# design.net
KiCad netlist of a schematic drawn in Altium Designer
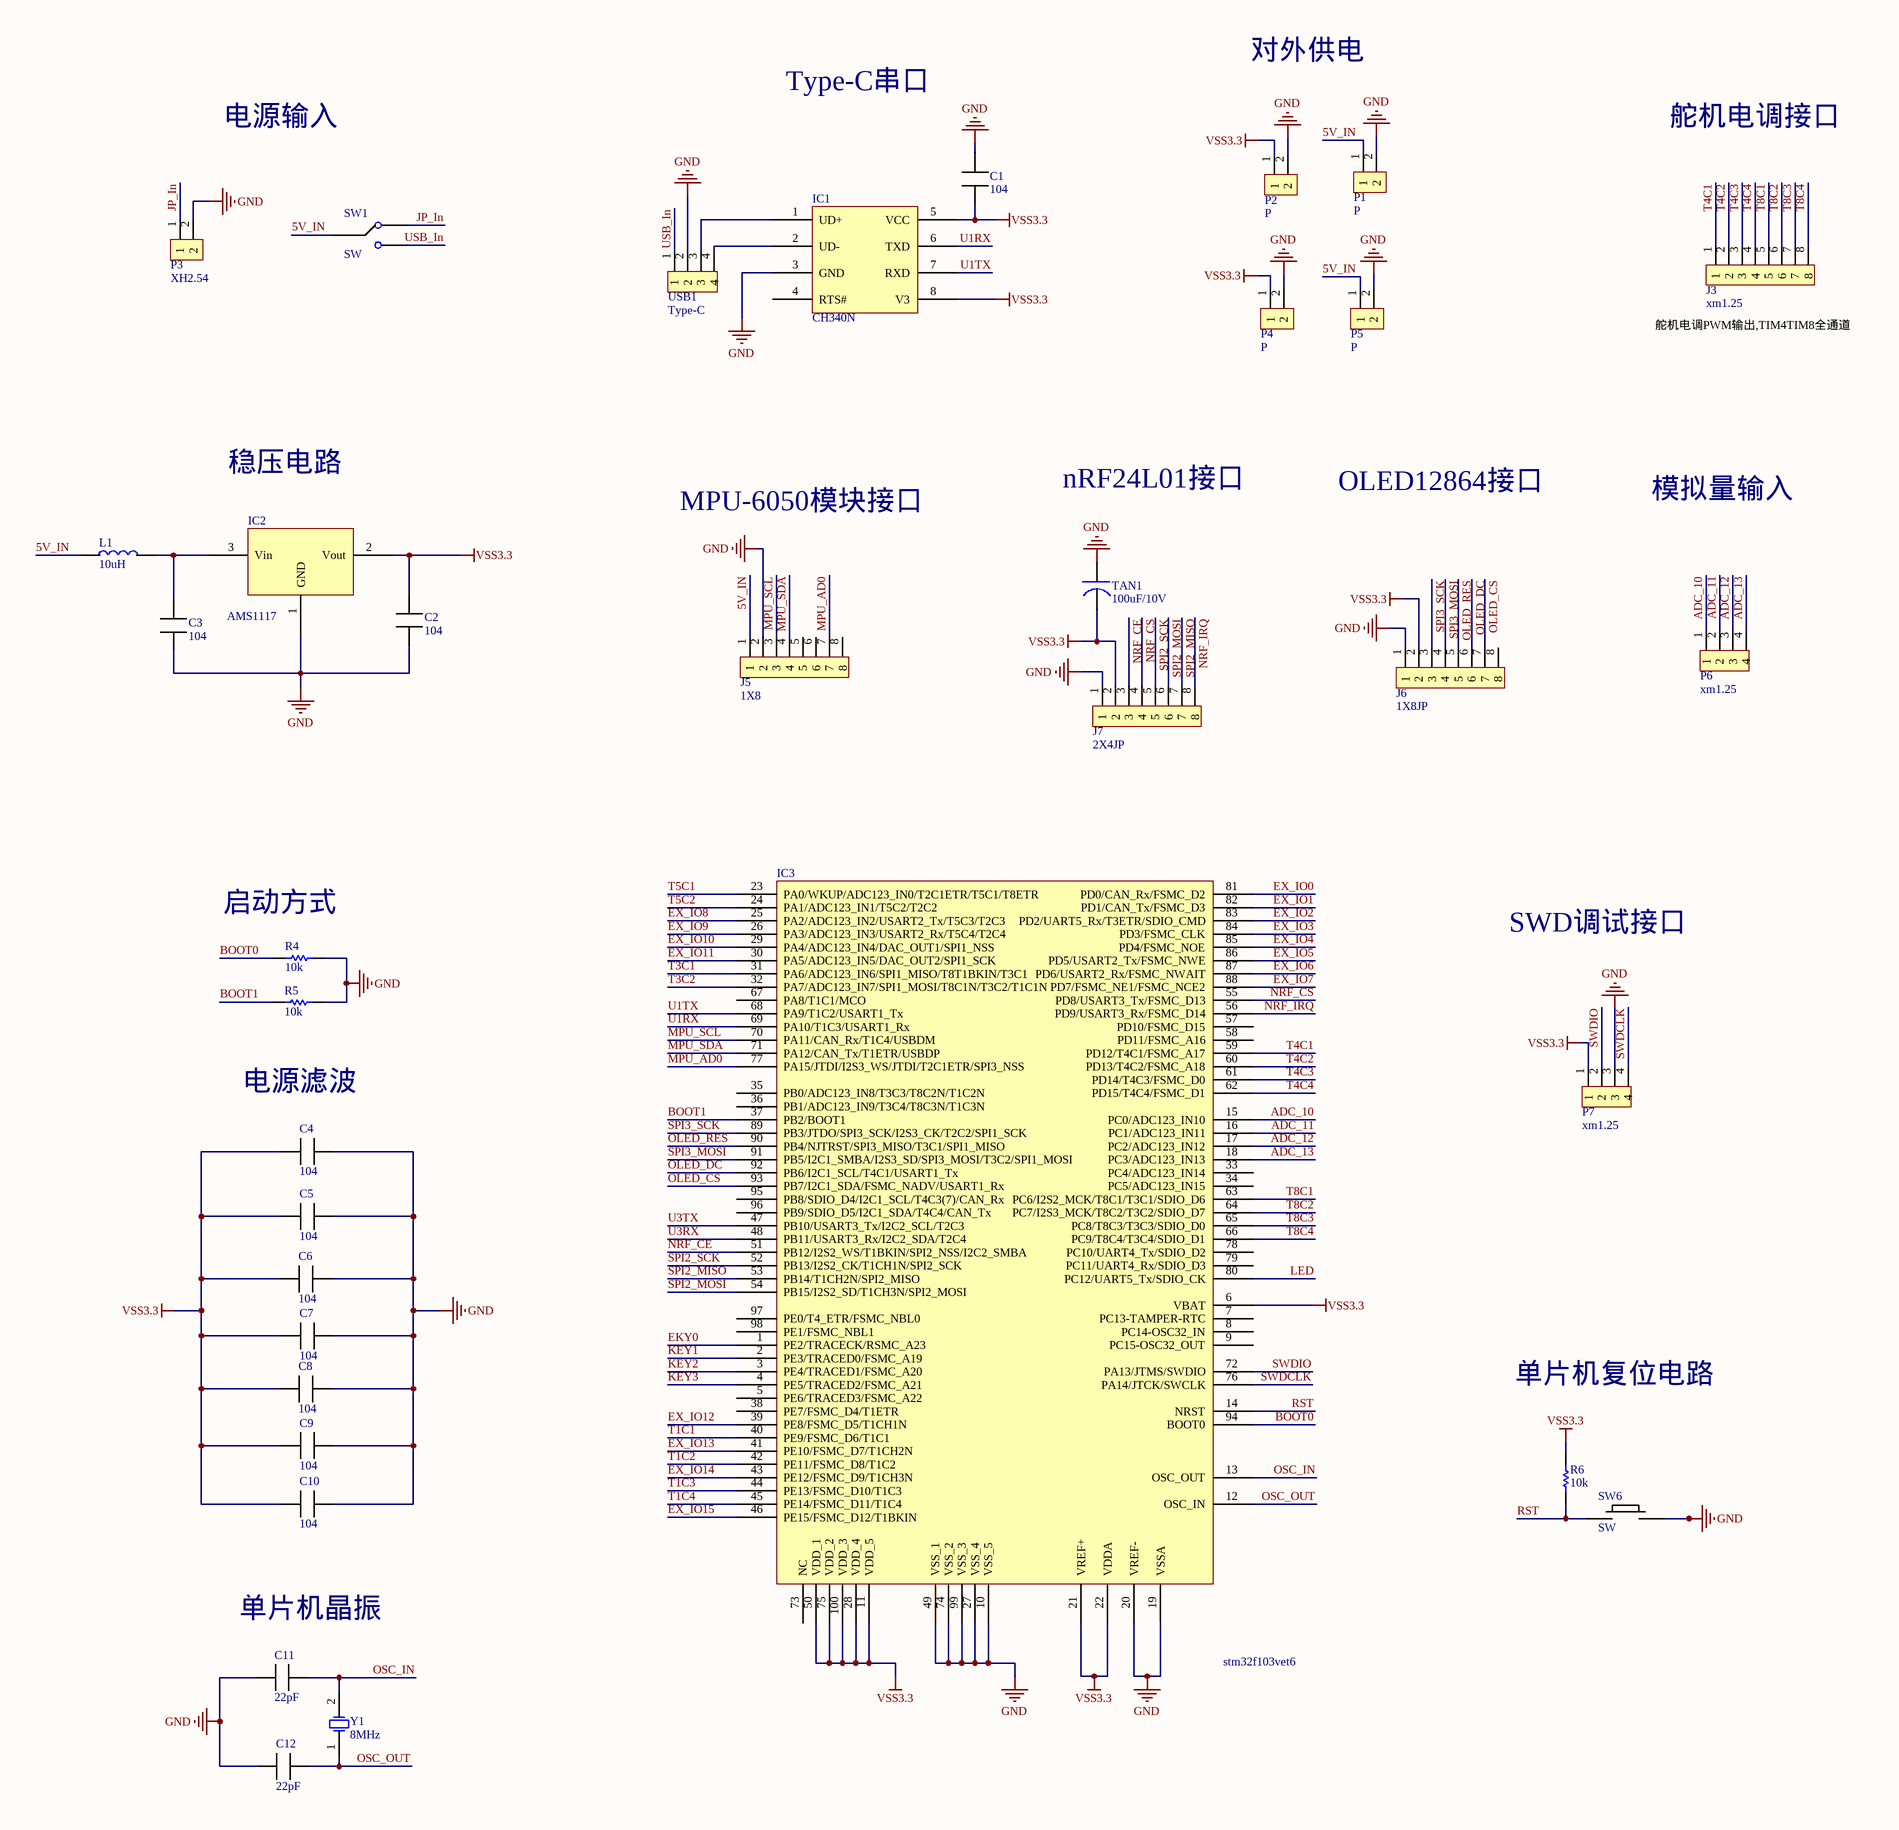
[diagram p0: 船核心板.SchDoc, left]
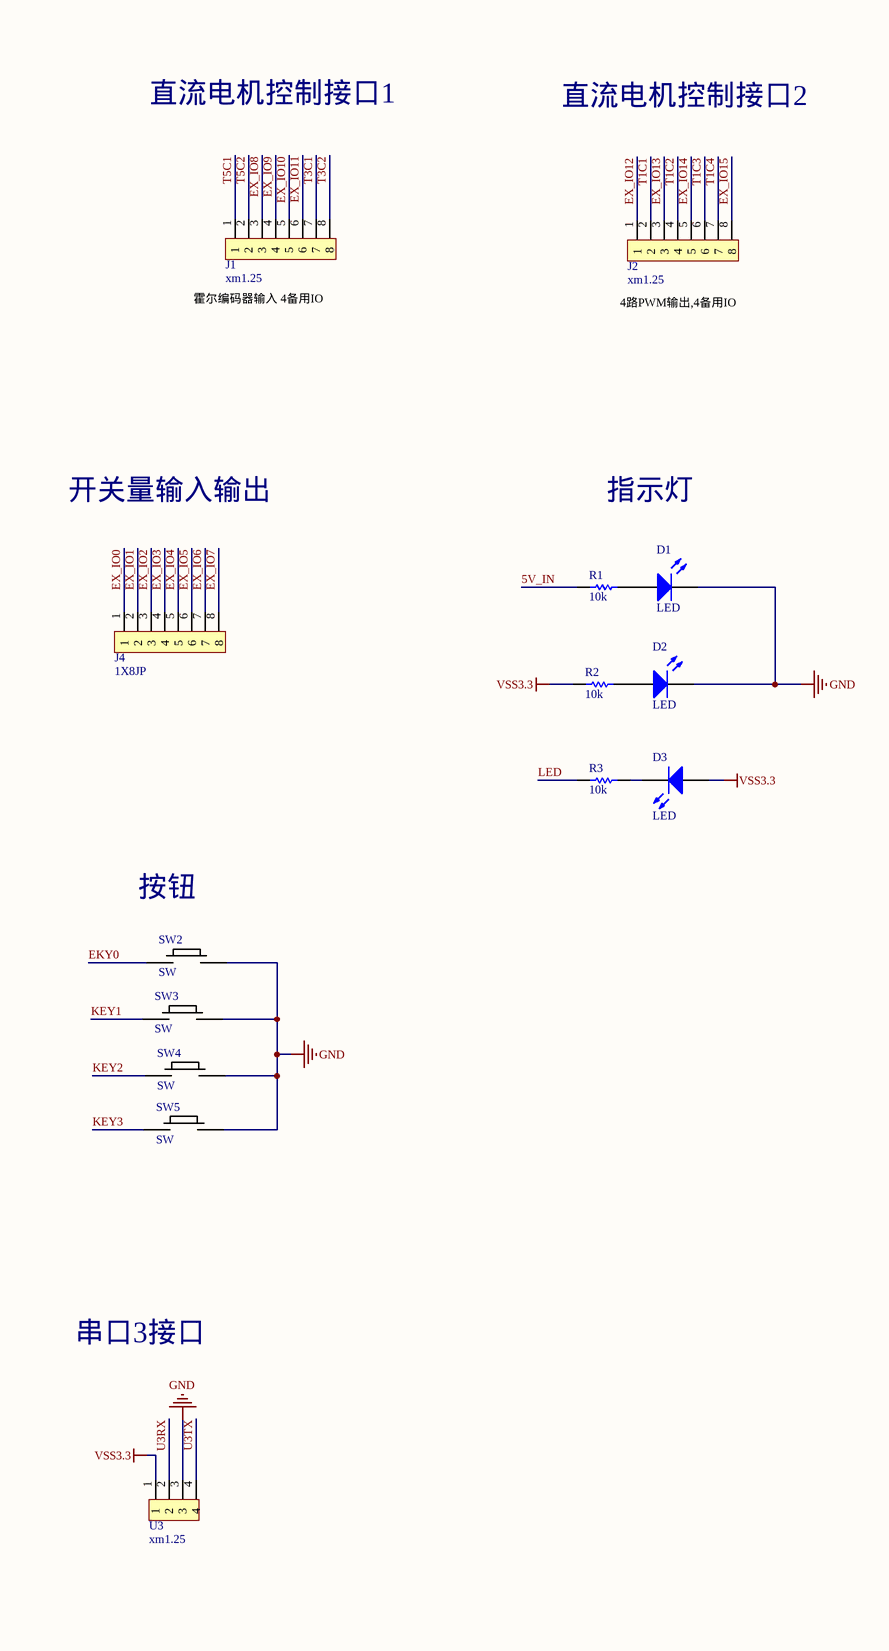
[diagram p1: 船核心板.SchDoc, right]

(export (version "E")
  (design (tool "Eeschema 10.0.6"))
  (components
    (comp (ref "C1") (value "104") (footprint "C 0603") (libsource (lib "船核心板") (part "电容")))
    (comp (ref "C2") (value "104") (footprint "C 0603") (libsource (lib "船核心板") (part "电容")))
    (comp (ref "C3") (value "104") (footprint "C 0603") (libsource (lib "船核心板") (part "电容")))
    (comp (ref "C4") (value "104") (footprint "C 0603") (libsource (lib "船核心板") (part "电容")))
    (comp (ref "C5") (value "104") (footprint "C 0603") (libsource (lib "船核心板") (part "电容")))
    (comp (ref "C6") (value "104") (footprint "C 0603") (libsource (lib "船核心板") (part "电容")))
    (comp (ref "C7") (value "104") (footprint "C 0603") (libsource (lib "船核心板") (part "电容")))
    (comp (ref "C8") (value "104") (footprint "C 0603") (libsource (lib "船核心板") (part "电容")))
    (comp (ref "C9") (value "104") (footprint "C 0603") (libsource (lib "船核心板") (part "电容")))
    (comp (ref "C10") (value "104") (footprint "C 0603") (libsource (lib "船核心板") (part "电容")))
    (comp (ref "C11") (value "22pF") (footprint "C 0603") (libsource (lib "船核心板") (part "电容")))
    (comp (ref "C12") (value "22pF") (footprint "C 0603") (libsource (lib "船核心板") (part "电容")))
    (comp (ref "D1")
      (value "LED")
      (footprint "LED 0603")
      (description "Typical INFRARED GaAs LED")
      (fields (field (name "PUBLISHER") "Altium Limited"))
      (libsource (lib "船核心板") (part "LED"))
    )
    (comp (ref "D2")
      (value "LED")
      (footprint "LED 0603")
      (description "Typical INFRARED GaAs LED")
      (fields (field (name "PUBLISHER") "Altium Limited"))
      (libsource (lib "船核心板") (part "LED"))
    )
    (comp (ref "D3")
      (value "LED")
      (footprint "LED 0603")
      (description "Typical INFRARED GaAs LED")
      (fields (field (name "PUBLISHER") "Altium Limited"))
      (libsource (lib "船核心板") (part "LED"))
    )
    (comp (ref "IC1") (value "CH340N") (footprint "SOP-8") (libsource (lib "船核心板") (part "CH340N")))
    (comp (ref "IC2") (value "AMS1117") (footprint "SOT-223") (libsource (lib "船核心板") (part "AMS1117-3.3")))
    (comp (ref "IC3")
      (value "stm32f103vet6")
      (footprint "LQPF100 12X12")
      (libsource (lib "altium-import") (part "root_0_stm32f103vet6_"))
    )
    (comp (ref "J1") (value "xm1.25") (footprint "MX1.25 8P") (libsource (lib "船核心板") (part "1X8排针")))
    (comp (ref "J2") (value "xm1.25") (footprint "MX1.25 8P") (libsource (lib "船核心板") (part "1X8排针")))
    (comp (ref "J3") (value "xm1.25") (footprint "MX1.25 8P") (libsource (lib "船核心板") (part "1X8排针")))
    (comp (ref "J4") (value "1X8JP") (footprint "HDR2.54-M-LI-8P") (libsource (lib "船核心板") (part "1X8排针")))
    (comp (ref "J5") (value "1X8") (footprint "HDR2.54-M-LI-8P") (libsource (lib "船核心板") (part "1X8排针")))
    (comp (ref "J6") (value "1X8JP") (footprint "HDR2.54-M-LI-8P") (libsource (lib "船核心板") (part "1X8排针")))
    (comp (ref "J7") (value "2X4JP") (footprint "HDR2.54-LI-2x4P") (libsource (lib "船核心板") (part "1X8排针")))
    (comp (ref "L1") (value "10uH") (footprint "L 0603") (libsource (lib "船核心板") (part "电感")))
    (comp (ref "P1") (value "P") (footprint "XH2.54 2P") (libsource (lib "船核心板") (part "1X2排针")))
    (comp (ref "P2") (value "P") (footprint "XH2.54 2P") (libsource (lib "船核心板") (part "1X2排针")))
    (comp (ref "P3") (value "XH2.54") (footprint "XH2.54 2P") (libsource (lib "船核心板") (part "1X2排针")))
    (comp (ref "P4") (value "P") (footprint "XH2.54 2P") (libsource (lib "船核心板") (part "1X2排针")))
    (comp (ref "P5") (value "P") (footprint "XH2.54 2P") (libsource (lib "船核心板") (part "1X2排针")))
    (comp (ref "P6") (value "xm1.25") (footprint "MX1.25") (libsource (lib "船核心板") (part "1X4排针")))
    (comp (ref "P7") (value "xm1.25") (footprint "MX1.25") (libsource (lib "船核心板") (part "1X4排针")))
    (comp (ref "R1")
      (value "10k")
      (footprint "R 0603")
      (description "Resistor")
      (fields (field (name "PUBLISHER") "Altium Limited"))
      (libsource (lib "船核心板") (part "Res"))
    )
    (comp (ref "R2")
      (value "10k")
      (footprint "R 0603")
      (description "Resistor")
      (fields (field (name "PUBLISHER") "Altium Limited"))
      (libsource (lib "船核心板") (part "Res"))
    )
    (comp (ref "R3")
      (value "10k")
      (footprint "R 0603")
      (description "Resistor")
      (fields (field (name "PUBLISHER") "Altium Limited"))
      (libsource (lib "船核心板") (part "Res"))
    )
    (comp (ref "R4")
      (value "10k")
      (footprint "R 0603")
      (description "Resistor")
      (fields (field (name "PUBLISHER") "Altium Limited"))
      (libsource (lib "船核心板") (part "Res"))
    )
    (comp (ref "R5")
      (value "10k")
      (footprint "R 0603")
      (description "Resistor")
      (fields (field (name "PUBLISHER") "Altium Limited"))
      (libsource (lib "船核心板") (part "Res"))
    )
    (comp (ref "R6")
      (value "10k")
      (footprint "R 0603")
      (description "Resistor")
      (fields (field (name "PUBLISHER") "Altium Limited"))
      (libsource (lib "船核心板") (part "Res"))
    )
    (comp (ref "SW1") (value "SW") (footprint "拨动开关 9X3.5X3.5 侧卧") (libsource (lib "船核心板") (part "单刀双置开关")))
    (comp (ref "SW2") (value "SW") (footprint "SW SMD 3x6x2.5") (libsource (lib "船核心板") (part "弹簧开关")))
    (comp (ref "SW3") (value "SW") (footprint "SW SMD 3x6x2.5") (libsource (lib "船核心板") (part "弹簧开关")))
    (comp (ref "SW4") (value "SW") (footprint "SW SMD 3x6x2.5") (libsource (lib "船核心板") (part "弹簧开关")))
    (comp (ref "SW5") (value "SW") (footprint "SW SMD 3x6x2.5") (libsource (lib "船核心板") (part "弹簧开关")))
    (comp (ref "SW6") (value "SW") (footprint "SW SMD 3x6x2.5") (libsource (lib "船核心板") (part "弹簧开关")))
    (comp (ref "TAN1")
      (value "100uF/10V")
      (footprint "6.3*5.4mm 电解电容")
      (libsource (lib "船核心板") (part "极性电容"))
    )
    (comp (ref "U3") (value "xm1.25") (footprint "2.54 _ 4Pin") (libsource (lib "船核心板") (part "1X4排针")))
    (comp (ref "USB1") (value "Type-C") (footprint "USB Type-C") (libsource (lib "船核心板") (part "1X4排针")))
    (comp (ref "Y1")
      (value "8MHz")
      (footprint "OSC SMD")
      (description "Crystal Oscillator")
      (fields (field (name "PUBLISHER") "Altium Limited"))
      (libsource (lib "船核心板") (part "晶振"))
    )
  )
  (nets
    (net (code "1") (name "/5V_IN") (class "Default")
      (node (ref "J5") (pin "1") (pinfunction "1_1") (pintype "passive"))
      (node (ref "L1") (pin "1") (pinfunction "1_1") (pintype "passive"))
      (node (ref "P1") (pin "1") (pinfunction "1_1") (pintype "passive"))
      (node (ref "P5") (pin "1") (pinfunction "1_1") (pintype "passive"))
      (node (ref "R1") (pin "1") (pinfunction "1_1") (pintype "passive"))
      (node (ref "SW1") (pin "1") (pinfunction "1_1") (pintype "passive"))
    )
    (net (code "2") (name "/ADC_10") (class "Default")
      (node (ref "IC3") (pin "15") (pinfunction "PC0/ADC123_IN10_15") (pintype "passive"))
      (node (ref "P6") (pin "1") (pinfunction "1_1") (pintype "passive"))
    )
    (net (code "3") (name "/ADC_11") (class "Default")
      (node (ref "IC3") (pin "16") (pinfunction "PC1/ADC123_IN11_16") (pintype "passive"))
      (node (ref "P6") (pin "2") (pinfunction "2_2") (pintype "passive"))
    )
    (net (code "4") (name "/ADC_12") (class "Default")
      (node (ref "IC3") (pin "17") (pinfunction "PC2/ADC123_IN12_17") (pintype "passive"))
      (node (ref "P6") (pin "3") (pinfunction "3_3") (pintype "passive"))
    )
    (net (code "5") (name "/ADC_13") (class "Default")
      (node (ref "IC3") (pin "18") (pinfunction "PC3/ADC123_IN13_18") (pintype "passive"))
      (node (ref "P6") (pin "4") (pinfunction "4_4") (pintype "passive"))
    )
    (net (code "6") (name "/BOOT0") (class "Default")
      (node (ref "IC3") (pin "94") (pinfunction "BOOT0_94") (pintype "passive"))
      (node (ref "R4") (pin "1") (pinfunction "1_1") (pintype "passive"))
    )
    (net (code "7") (name "/BOOT1") (class "Default")
      (node (ref "IC3") (pin "37") (pinfunction "PB2/BOOT1_37") (pintype "passive"))
      (node (ref "R5") (pin "1") (pinfunction "1_1") (pintype "passive"))
    )
    (net (code "8") (name "/EKY0") (class "Default")
      (node (ref "IC3") (pin "1") (pinfunction "PE2/TRACECK/RSMC_A23_1") (pintype "passive"))
      (node (ref "SW2") (pin "1") (pinfunction "1_1") (pintype "passive"))
    )
    (net (code "9") (name "/EX_IO0") (class "Default")
      (node (ref "IC3") (pin "81") (pinfunction "PD0/CAN_Rx/FSMC_D2_81") (pintype "passive"))
      (node (ref "J4") (pin "1") (pinfunction "1_1") (pintype "passive"))
    )
    (net (code "10") (name "/EX_IO1") (class "Default")
      (node (ref "IC3") (pin "82") (pinfunction "PD1/CAN_Tx/FSMC_D3_82") (pintype "passive"))
      (node (ref "J4") (pin "2") (pinfunction "2_2") (pintype "passive"))
    )
    (net (code "11") (name "/EX_IO2") (class "Default")
      (node (ref "IC3") (pin "83") (pinfunction "PD2/UART5_Rx/T3ETR/SDIO_CMD_83") (pintype "passive"))
      (node (ref "J4") (pin "3") (pinfunction "3_3") (pintype "passive"))
    )
    (net (code "12") (name "/EX_IO3") (class "Default")
      (node (ref "IC3") (pin "84") (pinfunction "PD3/FSMC_CLK_84") (pintype "passive"))
      (node (ref "J4") (pin "4") (pinfunction "4_4") (pintype "passive"))
    )
    (net (code "13") (name "/EX_IO4") (class "Default")
      (node (ref "IC3") (pin "85") (pinfunction "PD4/FSMC_NOE_85") (pintype "passive"))
      (node (ref "J4") (pin "5") (pinfunction "5_5") (pintype "passive"))
    )
    (net (code "14") (name "/EX_IO5") (class "Default")
      (node (ref "IC3") (pin "86") (pinfunction "PD5/USART2_Tx/FSMC_NWE_86") (pintype "passive"))
      (node (ref "J4") (pin "6") (pinfunction "6_6") (pintype "passive"))
    )
    (net (code "15") (name "/EX_IO6") (class "Default")
      (node (ref "IC3") (pin "87") (pinfunction "PD6/USART2_Rx/FSMC_NWAIT_87") (pintype "passive"))
      (node (ref "J4") (pin "7") (pinfunction "7_7") (pintype "passive"))
    )
    (net (code "16") (name "/EX_IO7") (class "Default")
      (node (ref "IC3") (pin "88") (pinfunction "PD7/FSMC_NE1/FSMC_NCE2_88") (pintype "passive"))
      (node (ref "J4") (pin "8") (pinfunction "8_8") (pintype "passive"))
    )
    (net (code "17") (name "/EX_IO8") (class "Default")
      (node (ref "IC3") (pin "25") (pinfunction "PA2/ADC123_IN2/USART2_Tx/T5C3/T2C3_25") (pintype "passive"))
      (node (ref "J1") (pin "3") (pinfunction "3_3") (pintype "passive"))
    )
    (net (code "18") (name "/EX_IO9") (class "Default")
      (node (ref "IC3") (pin "26") (pinfunction "PA3/ADC123_IN3/USART2_Rx/T5C4/T2C4_26") (pintype "passive"))
      (node (ref "J1") (pin "4") (pinfunction "4_4") (pintype "passive"))
    )
    (net (code "19") (name "/EX_IO10") (class "Default")
      (node (ref "IC3") (pin "29") (pinfunction "PA4/ADC123_IN4/DAC_OUT1/SPI1_NSS_29") (pintype "passive"))
      (node (ref "J1") (pin "5") (pinfunction "5_5") (pintype "passive"))
    )
    (net (code "20") (name "/EX_IO11") (class "Default")
      (node (ref "IC3") (pin "30") (pinfunction "PA5/ADC123_IN5/DAC_OUT2/SPI1_SCK_30") (pintype "passive"))
      (node (ref "J1") (pin "6") (pinfunction "6_6") (pintype "passive"))
    )
    (net (code "21") (name "/EX_IO12") (class "Default")
      (node (ref "IC3") (pin "39") (pinfunction "PE8/FSMC_D5/T1CH1N_39") (pintype "passive"))
      (node (ref "J2") (pin "1") (pinfunction "1_1") (pintype "passive"))
    )
    (net (code "22") (name "/EX_IO13") (class "Default")
      (node (ref "IC3") (pin "41") (pinfunction "PE10/FSMC_D7/T1CH2N_41") (pintype "passive"))
      (node (ref "J2") (pin "3") (pinfunction "3_3") (pintype "passive"))
    )
    (net (code "23") (name "/EX_IO14") (class "Default")
      (node (ref "IC3") (pin "43") (pinfunction "PE12/FSMC_D9/T1CH3N_43") (pintype "passive"))
      (node (ref "J2") (pin "5") (pinfunction "5_5") (pintype "passive"))
    )
    (net (code "24") (name "/EX_IO15") (class "Default")
      (node (ref "IC3") (pin "46") (pinfunction "PE15/FSMC_D12/T1BKIN_46") (pintype "passive"))
      (node (ref "J2") (pin "8") (pinfunction "8_8") (pintype "passive"))
    )
    (net (code "25") (name "/JP_In") (class "Default")
      (node (ref "P3") (pin "1") (pinfunction "1_1") (pintype "passive"))
      (node (ref "SW1") (pin "2") (pinfunction "2_2") (pintype "passive"))
    )
    (net (code "26") (name "/KEY1") (class "Default")
      (node (ref "IC3") (pin "2") (pinfunction "PE3/TRACED0/FSMC_A19_2") (pintype "passive"))
      (node (ref "SW3") (pin "1") (pinfunction "1_1") (pintype "passive"))
    )
    (net (code "27") (name "/KEY2") (class "Default")
      (node (ref "IC3") (pin "3") (pinfunction "PE4/TRACED1/FSMC_A20_3") (pintype "passive"))
      (node (ref "SW4") (pin "1") (pinfunction "1_1") (pintype "passive"))
    )
    (net (code "28") (name "/KEY3") (class "Default")
      (node (ref "IC3") (pin "4") (pinfunction "PE5/TRACED2/FSMC_A21_4") (pintype "passive"))
      (node (ref "SW5") (pin "1") (pinfunction "1_1") (pintype "passive"))
    )
    (net (code "29") (name "/LED") (class "Default")
      (node (ref "IC3") (pin "80") (pinfunction "PC12/UART5_Tx/SDIO_CK_80") (pintype "passive"))
      (node (ref "R3") (pin "1") (pinfunction "1_1") (pintype "passive"))
    )
    (net (code "30") (name "/MPU_AD0") (class "Default")
      (node (ref "IC3") (pin "77") (pinfunction "PA15/JTDI/I2S3_WS/JTDI/T2C1ETR/SPI3_NSS_77") (pintype "passive"))
      (node (ref "J5") (pin "7") (pinfunction "7_7") (pintype "passive"))
    )
    (net (code "31") (name "/MPU_SCL") (class "Default")
      (node (ref "IC3") (pin "70") (pinfunction "PA11/CAN_Rx/T1C4/USBDM_70") (pintype "passive"))
      (node (ref "J5") (pin "3") (pinfunction "3_3") (pintype "passive"))
    )
    (net (code "32") (name "/MPU_SDA") (class "Default")
      (node (ref "IC3") (pin "71") (pinfunction "PA12/CAN_Tx/T1ETR/USBDP_71") (pintype "passive"))
      (node (ref "J5") (pin "4") (pinfunction "4_4") (pintype "passive"))
    )
    (net (code "33") (name "/NRF_CE") (class "Default")
      (node (ref "IC3") (pin "51") (pinfunction "PB12/I2S2_WS/T1BKIN/SPI2_NSS/I2C2_SMBA_51") (pintype "passive"))
      (node (ref "J7") (pin "3") (pinfunction "3_3") (pintype "passive"))
    )
    (net (code "34") (name "/NRF_CS") (class "Default")
      (node (ref "IC3") (pin "55") (pinfunction "PD8/USART3_Tx/FSMC_D13_55") (pintype "passive"))
      (node (ref "J7") (pin "4") (pinfunction "4_4") (pintype "passive"))
    )
    (net (code "35") (name "/NRF_IRQ") (class "Default")
      (node (ref "IC3") (pin "56") (pinfunction "PD9/USART3_Rx/FSMC_D14_56") (pintype "passive"))
      (node (ref "J7") (pin "8") (pinfunction "8_8") (pintype "passive"))
    )
    (net (code "36") (name "/OLED_CS") (class "Default")
      (node (ref "IC3") (pin "93") (pinfunction "PB7/I2C1_SDA/FSMC_NADV/USART1_Rx_93") (pintype "passive"))
      (node (ref "J6") (pin "7") (pinfunction "7_7") (pintype "passive"))
    )
    (net (code "37") (name "/OLED_DC") (class "Default")
      (node (ref "IC3") (pin "92") (pinfunction "PB6/I2C1_SCL/T4C1/USART1_Tx_92") (pintype "passive"))
      (node (ref "J6") (pin "6") (pinfunction "6_6") (pintype "passive"))
    )
    (net (code "38") (name "/OLED_RES") (class "Default")
      (node (ref "IC3") (pin "90") (pinfunction "PB4/NJTRST/SPI3_MISO/T3C1/SPI1_MISO_90") (pintype "passive"))
      (node (ref "J6") (pin "5") (pinfunction "5_5") (pintype "passive"))
    )
    (net (code "39") (name "/OSC_IN") (class "Default")
      (node (ref "C11") (pin "2") (pinfunction "2_2") (pintype "passive"))
      (node (ref "IC3") (pin "13") (pinfunction "OSC_OUT_13") (pintype "passive"))
      (node (ref "Y1") (pin "2") (pinfunction "OSC2_2") (pintype "passive"))
    )
    (net (code "40") (name "/OSC_OUT") (class "Default")
      (node (ref "C12") (pin "2") (pinfunction "2_2") (pintype "passive"))
      (node (ref "IC3") (pin "12") (pinfunction "OSC_IN_12") (pintype "passive"))
      (node (ref "Y1") (pin "1") (pinfunction "OSC1_1") (pintype "passive"))
    )
    (net (code "41") (name "/RST") (class "Default")
      (node (ref "IC3") (pin "14") (pinfunction "NRST_14") (pintype "passive"))
      (node (ref "R6") (pin "1") (pinfunction "1_1") (pintype "passive"))
      (node (ref "SW6") (pin "1") (pinfunction "1_1") (pintype "passive"))
    )
    (net (code "42") (name "/SPI2_MISO") (class "Default")
      (node (ref "IC3") (pin "53") (pinfunction "PB14/T1CH2N/SPI2_MISO_53") (pintype "passive"))
      (node (ref "J7") (pin "7") (pinfunction "7_7") (pintype "passive"))
    )
    (net (code "43") (name "/SPI2_MOSI") (class "Default")
      (node (ref "IC3") (pin "54") (pinfunction "PB15/I2S2_SD/T1CH3N/SPI2_MOSI_54") (pintype "passive"))
      (node (ref "J7") (pin "6") (pinfunction "6_6") (pintype "passive"))
    )
    (net (code "44") (name "/SPI2_SCK") (class "Default")
      (node (ref "IC3") (pin "52") (pinfunction "PB13/I2S2_CK/T1CH1N/SPI2_SCK_52") (pintype "passive"))
      (node (ref "J7") (pin "5") (pinfunction "5_5") (pintype "passive"))
    )
    (net (code "45") (name "/SPI3_MOSI") (class "Default")
      (node (ref "IC3") (pin "91") (pinfunction "PB5/I2C1_SMBA/I2S3_SD/SPI3_MOSI/T3C2/SPI1_MOSI_91") (pintype "passive"))
      (node (ref "J6") (pin "4") (pinfunction "4_4") (pintype "passive"))
    )
    (net (code "46") (name "/SPI3_SCK") (class "Default")
      (node (ref "IC3") (pin "89") (pinfunction "PB3/JTDO/SPI3_SCK/I2S3_CK/T2C2/SPI1_SCK_89") (pintype "passive"))
      (node (ref "J6") (pin "3") (pinfunction "3_3") (pintype "passive"))
    )
    (net (code "47") (name "/SWDCLK") (class "Default")
      (node (ref "IC3") (pin "76") (pinfunction "PA14/JTCK/SWCLK_76") (pintype "passive"))
      (node (ref "P7") (pin "4") (pinfunction "4_4") (pintype "passive"))
    )
    (net (code "48") (name "/SWDIO") (class "Default")
      (node (ref "IC3") (pin "72") (pinfunction "PA13/JTMS/SWDIO_72") (pintype "passive"))
      (node (ref "P7") (pin "2") (pinfunction "2_2") (pintype "passive"))
    )
    (net (code "49") (name "/T1C1") (class "Default")
      (node (ref "IC3") (pin "40") (pinfunction "PE9/FSMC_D6/T1C1_40") (pintype "passive"))
      (node (ref "J2") (pin "2") (pinfunction "2_2") (pintype "passive"))
    )
    (net (code "50") (name "/T1C2") (class "Default")
      (node (ref "IC3") (pin "42") (pinfunction "PE11/FSMC_D8/T1C2_42") (pintype "passive"))
      (node (ref "J2") (pin "4") (pinfunction "4_4") (pintype "passive"))
    )
    (net (code "51") (name "/T1C3") (class "Default")
      (node (ref "IC3") (pin "44") (pinfunction "PE13/FSMC_D10/T1C3_44") (pintype "passive"))
      (node (ref "J2") (pin "6") (pinfunction "6_6") (pintype "passive"))
    )
    (net (code "52") (name "/T1C4") (class "Default")
      (node (ref "IC3") (pin "45") (pinfunction "PE14/FSMC_D11/T1C4_45") (pintype "passive"))
      (node (ref "J2") (pin "7") (pinfunction "7_7") (pintype "passive"))
    )
    (net (code "53") (name "/T3C1") (class "Default")
      (node (ref "IC3") (pin "31") (pinfunction "PA6/ADC123_IN6/SPI1_MISO/T8T1BKIN/T3C1_31") (pintype "passive"))
      (node (ref "J1") (pin "7") (pinfunction "7_7") (pintype "passive"))
    )
    (net (code "54") (name "/T3C2") (class "Default")
      (node (ref "IC3") (pin "32") (pinfunction "PA7/ADC123_IN7/SPI1_MOSI/T8C1N/T3C2/T1C1N_32") (pintype "passive"))
      (node (ref "J1") (pin "8") (pinfunction "8_8") (pintype "passive"))
    )
    (net (code "55") (name "/T4C1") (class "Default")
      (node (ref "IC3") (pin "59") (pinfunction "PD12/T4C1/FSMC_A17_59") (pintype "passive"))
      (node (ref "J3") (pin "1") (pinfunction "1_1") (pintype "passive"))
    )
    (net (code "56") (name "/T4C2") (class "Default")
      (node (ref "IC3") (pin "60") (pinfunction "PD13/T4C2/FSMC_A18_60") (pintype "passive"))
      (node (ref "J3") (pin "2") (pinfunction "2_2") (pintype "passive"))
    )
    (net (code "57") (name "/T4C3") (class "Default")
      (node (ref "IC3") (pin "61") (pinfunction "PD14/T4C3/FSMC_D0_61") (pintype "passive"))
      (node (ref "J3") (pin "3") (pinfunction "3_3") (pintype "passive"))
    )
    (net (code "58") (name "/T4C4") (class "Default")
      (node (ref "IC3") (pin "62") (pinfunction "PD15/T4C4/FSMC_D1_62") (pintype "passive"))
      (node (ref "J3") (pin "4") (pinfunction "4_4") (pintype "passive"))
    )
    (net (code "59") (name "/T5C1") (class "Default")
      (node (ref "IC3") (pin "23") (pinfunction "PA0/WKUP/ADC123_IN0/T2C1ETR/T5C1/T8ETR_23") (pintype "passive"))
      (node (ref "J1") (pin "1") (pinfunction "1_1") (pintype "passive"))
    )
    (net (code "60") (name "/T5C2") (class "Default")
      (node (ref "IC3") (pin "24") (pinfunction "PA1/ADC123_IN1/T5C2/T2C2_24") (pintype "passive"))
      (node (ref "J1") (pin "2") (pinfunction "2_2") (pintype "passive"))
    )
    (net (code "61") (name "/T8C1") (class "Default")
      (node (ref "IC3") (pin "63") (pinfunction "PC6/I2S2_MCK/T8C1/T3C1/SDIO_D6_63") (pintype "passive"))
      (node (ref "J3") (pin "5") (pinfunction "5_5") (pintype "passive"))
    )
    (net (code "62") (name "/T8C2") (class "Default")
      (node (ref "IC3") (pin "64") (pinfunction "PC7/I2S3_MCK/T8C2/T3C2/SDIO_D7_64") (pintype "passive"))
      (node (ref "J3") (pin "6") (pinfunction "6_6") (pintype "passive"))
    )
    (net (code "63") (name "/T8C3") (class "Default")
      (node (ref "IC3") (pin "65") (pinfunction "PC8/T8C3/T3C3/SDIO_D0_65") (pintype "passive"))
      (node (ref "J3") (pin "7") (pinfunction "7_7") (pintype "passive"))
    )
    (net (code "64") (name "/T8C4") (class "Default")
      (node (ref "IC3") (pin "66") (pinfunction "PC9/T8C4/T3C4/SDIO_D1_66") (pintype "passive"))
      (node (ref "J3") (pin "8") (pinfunction "8_8") (pintype "passive"))
    )
    (net (code "65") (name "/U1RX") (class "Default")
      (node (ref "IC1") (pin "6") (pinfunction "TXD_6") (pintype "passive"))
      (node (ref "IC3") (pin "69") (pinfunction "PA10/T1C3/USART1_Rx_69") (pintype "passive"))
    )
    (net (code "66") (name "/U1TX") (class "Default")
      (node (ref "IC1") (pin "7") (pinfunction "RXD_7") (pintype "passive"))
      (node (ref "IC3") (pin "68") (pinfunction "PA9/T1C2/USART1_Tx_68") (pintype "passive"))
    )
    (net (code "67") (name "/U3RX") (class "Default")
      (node (ref "IC3") (pin "48") (pinfunction "PB11/USART3_Rx/I2C2_SDA/T2C4_48") (pintype "passive"))
      (node (ref "U3") (pin "2") (pinfunction "2_2") (pintype "passive"))
    )
    (net (code "68") (name "/U3TX") (class "Default")
      (node (ref "IC3") (pin "47") (pinfunction "PB10/USART3_Tx/I2C2_SCL/T2C3_47") (pintype "passive"))
      (node (ref "U3") (pin "4") (pinfunction "4_4") (pintype "passive"))
    )
    (net (code "69") (name "/USB_In") (class "Default")
      (node (ref "SW1") (pin "3") (pinfunction "3_3") (pintype "passive"))
      (node (ref "USB1") (pin "1") (pinfunction "1_1") (pintype "passive"))
    )
    (net (code "70") (name "GND") (class "Default")
      (node (ref "C1") (pin "2") (pinfunction "2_2") (pintype "passive"))
      (node (ref "C10") (pin "2") (pinfunction "2_2") (pintype "passive"))
      (node (ref "C11") (pin "1") (pinfunction "1_1") (pintype "passive"))
      (node (ref "C12") (pin "1") (pinfunction "1_1") (pintype "passive"))
      (node (ref "C2") (pin "1") (pinfunction "1_1") (pintype "passive"))
      (node (ref "C3") (pin "1") (pinfunction "1_1") (pintype "passive"))
      (node (ref "C4") (pin "2") (pinfunction "2_2") (pintype "passive"))
      (node (ref "C5") (pin "2") (pinfunction "2_2") (pintype "passive"))
      (node (ref "C6") (pin "2") (pinfunction "2_2") (pintype "passive"))
      (node (ref "C7") (pin "2") (pinfunction "2_2") (pintype "passive"))
      (node (ref "C8") (pin "2") (pinfunction "2_2") (pintype "passive"))
      (node (ref "C9") (pin "2") (pinfunction "2_2") (pintype "passive"))
      (node (ref "D1") (pin "2") (pinfunction "K_2") (pintype "passive"))
      (node (ref "D2") (pin "2") (pinfunction "K_2") (pintype "passive"))
      (node (ref "IC1") (pin "3") (pinfunction "GND_3") (pintype "passive"))
      (node (ref "IC2") (pin "1") (pinfunction "GND_1") (pintype "passive"))
      (node (ref "IC3") (pin "10") (pinfunction "VSS_5_10") (pintype "passive"))
      (node (ref "IC3") (pin "19") (pinfunction "VSSA_19") (pintype "passive"))
      (node (ref "IC3") (pin "20") (pinfunction "VREF-_20") (pintype "passive"))
      (node (ref "IC3") (pin "27") (pinfunction "VSS_4_27") (pintype "passive"))
      (node (ref "IC3") (pin "49") (pinfunction "VSS_1_49") (pintype "passive"))
      (node (ref "IC3") (pin "74") (pinfunction "VSS_2_74") (pintype "passive"))
      (node (ref "IC3") (pin "99") (pinfunction "VSS_3_99") (pintype "passive"))
      (node (ref "J5") (pin "2") (pinfunction "2_2") (pintype "passive"))
      (node (ref "J6") (pin "1") (pinfunction "1_1") (pintype "passive"))
      (node (ref "J7") (pin "1") (pinfunction "1_1") (pintype "passive"))
      (node (ref "P1") (pin "2") (pinfunction "2_2") (pintype "passive"))
      (node (ref "P2") (pin "2") (pinfunction "2_2") (pintype "passive"))
      (node (ref "P3") (pin "2") (pinfunction "2_2") (pintype "passive"))
      (node (ref "P4") (pin "2") (pinfunction "2_2") (pintype "passive"))
      (node (ref "P5") (pin "2") (pinfunction "2_2") (pintype "passive"))
      (node (ref "P7") (pin "3") (pinfunction "3_3") (pintype "passive"))
      (node (ref "R4") (pin "2") (pinfunction "2_2") (pintype "passive"))
      (node (ref "R5") (pin "2") (pinfunction "2_2") (pintype "passive"))
      (node (ref "SW2") (pin "2") (pinfunction "2_2") (pintype "passive"))
      (node (ref "SW3") (pin "2") (pinfunction "2_2") (pintype "passive"))
      (node (ref "SW4") (pin "2") (pinfunction "2_2") (pintype "passive"))
      (node (ref "SW5") (pin "2") (pinfunction "2_2") (pintype "passive"))
      (node (ref "SW6") (pin "2") (pinfunction "2_2") (pintype "passive"))
      (node (ref "TAN1") (pin "2") (pinfunction "2_2") (pintype "passive"))
      (node (ref "U3") (pin "3") (pinfunction "3_3") (pintype "passive"))
      (node (ref "USB1") (pin "2") (pinfunction "2_2") (pintype "passive"))
    )
    (net (code "71") (name "Net-(D1-A)") (class "Default")
      (node (ref "D1") (pin "1") (pinfunction "A_1") (pintype "passive"))
      (node (ref "R1") (pin "2") (pinfunction "2_2") (pintype "passive"))
    )
    (net (code "72") (name "Net-(D2-A)") (class "Default")
      (node (ref "D2") (pin "1") (pinfunction "A_1") (pintype "passive"))
      (node (ref "R2") (pin "2") (pinfunction "2_2") (pintype "passive"))
    )
    (net (code "73") (name "Net-(D3-K)") (class "Default")
      (node (ref "D3") (pin "2") (pinfunction "K_2") (pintype "passive"))
      (node (ref "R3") (pin "2") (pinfunction "2_2") (pintype "passive"))
    )
    (net (code "74") (name "Net-(IC1-UD+)") (class "Default")
      (node (ref "IC1") (pin "1") (pinfunction "UD+_1") (pintype "passive"))
      (node (ref "USB1") (pin "3") (pinfunction "3_3") (pintype "passive"))
    )
    (net (code "75") (name "Net-(IC1-UD-)") (class "Default")
      (node (ref "IC1") (pin "2") (pinfunction "UD-_2") (pintype "passive"))
      (node (ref "USB1") (pin "4") (pinfunction "4_4") (pintype "passive"))
    )
    (net (code "76") (name "Net-(IC2-Vin)") (class "Default")
      (node (ref "C3") (pin "2") (pinfunction "2_2") (pintype "passive"))
      (node (ref "IC2") (pin "3") (pinfunction "Vin_3") (pintype "passive"))
      (node (ref "L1") (pin "2") (pinfunction "2_2") (pintype "passive"))
    )
    (net (code "77") (name "VSS3.3") (class "Default")
      (node (ref "C1") (pin "1") (pinfunction "1_1") (pintype "passive"))
      (node (ref "C10") (pin "1") (pinfunction "1_1") (pintype "passive"))
      (node (ref "C2") (pin "2") (pinfunction "2_2") (pintype "passive"))
      (node (ref "C4") (pin "1") (pinfunction "1_1") (pintype "passive"))
      (node (ref "C5") (pin "1") (pinfunction "1_1") (pintype "passive"))
      (node (ref "C6") (pin "1") (pinfunction "1_1") (pintype "passive"))
      (node (ref "C7") (pin "1") (pinfunction "1_1") (pintype "passive"))
      (node (ref "C8") (pin "1") (pinfunction "1_1") (pintype "passive"))
      (node (ref "C9") (pin "1") (pinfunction "1_1") (pintype "passive"))
      (node (ref "D3") (pin "1") (pinfunction "A_1") (pintype "passive"))
      (node (ref "IC1") (pin "5") (pinfunction "VCC_5") (pintype "passive"))
      (node (ref "IC1") (pin "8") (pinfunction "V3_8") (pintype "passive"))
      (node (ref "IC2") (pin "2") (pinfunction "Vout_2") (pintype "passive"))
      (node (ref "IC3") (pin "100") (pinfunction "VDD_3_100") (pintype "passive"))
      (node (ref "IC3") (pin "11") (pinfunction "VDD_5_11") (pintype "passive"))
      (node (ref "IC3") (pin "21") (pinfunction "VREF+_21") (pintype "passive"))
      (node (ref "IC3") (pin "22") (pinfunction "VDDA_22") (pintype "passive"))
      (node (ref "IC3") (pin "28") (pinfunction "VDD_4_28") (pintype "passive"))
      (node (ref "IC3") (pin "50") (pinfunction "VDD_1_50") (pintype "passive"))
      (node (ref "IC3") (pin "6") (pinfunction "VBAT_6") (pintype "passive"))
      (node (ref "IC3") (pin "75") (pinfunction "VDD_2_75") (pintype "passive"))
      (node (ref "J6") (pin "2") (pinfunction "2_2") (pintype "passive"))
      (node (ref "J7") (pin "2") (pinfunction "2_2") (pintype "passive"))
      (node (ref "P2") (pin "1") (pinfunction "1_1") (pintype "passive"))
      (node (ref "P4") (pin "1") (pinfunction "1_1") (pintype "passive"))
      (node (ref "P7") (pin "1") (pinfunction "1_1") (pintype "passive"))
      (node (ref "R2") (pin "1") (pinfunction "1_1") (pintype "passive"))
      (node (ref "R6") (pin "2") (pinfunction "2_2") (pintype "passive"))
      (node (ref "TAN1") (pin "1") (pinfunction "1_1") (pintype "passive"))
      (node (ref "U3") (pin "1") (pinfunction "1_1") (pintype "passive"))
    )
    (net (code "78") (name "unconnected-(IC1-RTS#-Pad4)") (class "Default")
      (node (ref "IC1") (pin "4") (pinfunction "RTS#_4") (pintype "passive"))
    )
    (net (code "79") (name "unconnected-(IC3-NC-Pad73)") (class "Default")
      (node (ref "IC3") (pin "73") (pinfunction "NC_73") (pintype "passive"))
    )
    (net (code "80") (name "unconnected-(IC3-PA8{slash}T1C1{slash}MCO-Pad67)") (class "Default")
      (node (ref "IC3") (pin "67") (pinfunction "PA8/T1C1/MCO_67") (pintype "passive"))
    )
    (net (code "81") (name "unconnected-(IC3-PB0{slash}ADC123_IN8{slash}T3C3{slash}T8C2N{slash}T1C2N-Pad35)") (class "Default")
      (node (ref "IC3") (pin "35") (pinfunction "PB0/ADC123_IN8/T3C3/T8C2N/T1C2N_35") (pintype "passive"))
    )
    (net (code "82") (name "unconnected-(IC3-PB1{slash}ADC123_IN9{slash}T3C4{slash}T8C3N{slash}T1C3N-Pad36)") (class "Default")
      (node (ref "IC3") (pin "36") (pinfunction "PB1/ADC123_IN9/T3C4/T8C3N/T1C3N_36") (pintype "passive"))
    )
    (net (code "83") (name "unconnected-(IC3-PB8{slash}SDIO_D4{slash}I2C1_SCL{slash}T4C3(7){slash}CAN_Rx-Pad95)") (class "Default")
      (node (ref "IC3") (pin "95") (pinfunction "PB8/SDIO_D4/I2C1_SCL/T4C3(7)/CAN_Rx_95") (pintype "passive"))
    )
    (net (code "84") (name "unconnected-(IC3-PB9{slash}SDIO_D5{slash}I2C1_SDA{slash}T4C4{slash}CAN_Tx-Pad96)") (class "Default")
      (node (ref "IC3") (pin "96") (pinfunction "PB9/SDIO_D5/I2C1_SDA/T4C4/CAN_Tx_96") (pintype "passive"))
    )
    (net (code "85") (name "unconnected-(IC3-PC4{slash}ADC123_IN14-Pad33)") (class "Default")
      (node (ref "IC3") (pin "33") (pinfunction "PC4/ADC123_IN14_33") (pintype "passive"))
    )
    (net (code "86") (name "unconnected-(IC3-PC5{slash}ADC123_IN15-Pad34)") (class "Default")
      (node (ref "IC3") (pin "34") (pinfunction "PC5/ADC123_IN15_34") (pintype "passive"))
    )
    (net (code "87") (name "unconnected-(IC3-PC10{slash}UART4_Tx{slash}SDIO_D2-Pad78)") (class "Default")
      (node (ref "IC3") (pin "78") (pinfunction "PC10/UART4_Tx/SDIO_D2_78") (pintype "passive"))
    )
    (net (code "88") (name "unconnected-(IC3-PC11{slash}UART4_Rx{slash}SDIO_D3-Pad79)") (class "Default")
      (node (ref "IC3") (pin "79") (pinfunction "PC11/UART4_Rx/SDIO_D3_79") (pintype "passive"))
    )
    (net (code "89") (name "unconnected-(IC3-PC13-TAMPER-RTC-Pad7)") (class "Default")
      (node (ref "IC3") (pin "7") (pinfunction "PC13-TAMPER-RTC_7") (pintype "passive"))
    )
    (net (code "90") (name "unconnected-(IC3-PC14-OSC32_IN-Pad8)") (class "Default")
      (node (ref "IC3") (pin "8") (pinfunction "PC14-OSC32_IN_8") (pintype "passive"))
    )
    (net (code "91") (name "unconnected-(IC3-PC15-OSC32_OUT-Pad9)") (class "Default")
      (node (ref "IC3") (pin "9") (pinfunction "PC15-OSC32_OUT_9") (pintype "passive"))
    )
    (net (code "92") (name "unconnected-(IC3-PD10{slash}FSMC_D15-Pad57)") (class "Default")
      (node (ref "IC3") (pin "57") (pinfunction "PD10/FSMC_D15_57") (pintype "passive"))
    )
    (net (code "93") (name "unconnected-(IC3-PD11{slash}FSMC_A16-Pad58)") (class "Default")
      (node (ref "IC3") (pin "58") (pinfunction "PD11/FSMC_A16_58") (pintype "passive"))
    )
    (net (code "94") (name "unconnected-(IC3-PE0{slash}T4_ETR{slash}FSMC_NBL0-Pad97)") (class "Default")
      (node (ref "IC3") (pin "97") (pinfunction "PE0/T4_ETR/FSMC_NBL0_97") (pintype "passive"))
    )
    (net (code "95") (name "unconnected-(IC3-PE1{slash}FSMC_NBL1-Pad98)") (class "Default")
      (node (ref "IC3") (pin "98") (pinfunction "PE1/FSMC_NBL1_98") (pintype "passive"))
    )
    (net (code "96") (name "unconnected-(IC3-PE6{slash}TRACED3{slash}FSMC_A22-Pad5)") (class "Default")
      (node (ref "IC3") (pin "5") (pinfunction "PE6/TRACED3/FSMC_A22_5") (pintype "passive"))
    )
    (net (code "97") (name "unconnected-(IC3-PE7{slash}FSMC_D4{slash}T1ETR-Pad38)") (class "Default")
      (node (ref "IC3") (pin "38") (pinfunction "PE7/FSMC_D4/T1ETR_38") (pintype "passive"))
    )
    (net (code "98") (name "unconnected-(J5-Pad5)") (class "Default")
      (node (ref "J5") (pin "5") (pinfunction "5_5") (pintype "passive"))
    )
    (net (code "99") (name "unconnected-(J5-Pad6)") (class "Default")
      (node (ref "J5") (pin "6") (pinfunction "6_6") (pintype "passive"))
    )
    (net (code "100") (name "unconnected-(J5-Pad8)") (class "Default")
      (node (ref "J5") (pin "8") (pinfunction "8_8") (pintype "passive"))
    )
    (net (code "101") (name "unconnected-(J6-Pad8)") (class "Default")
      (node (ref "J6") (pin "8") (pinfunction "8_8") (pintype "passive"))
    )
  )
)
